# Brickster_8884bt_Receiver.net
KiCad netlist of a schematic drawn in EAGLE
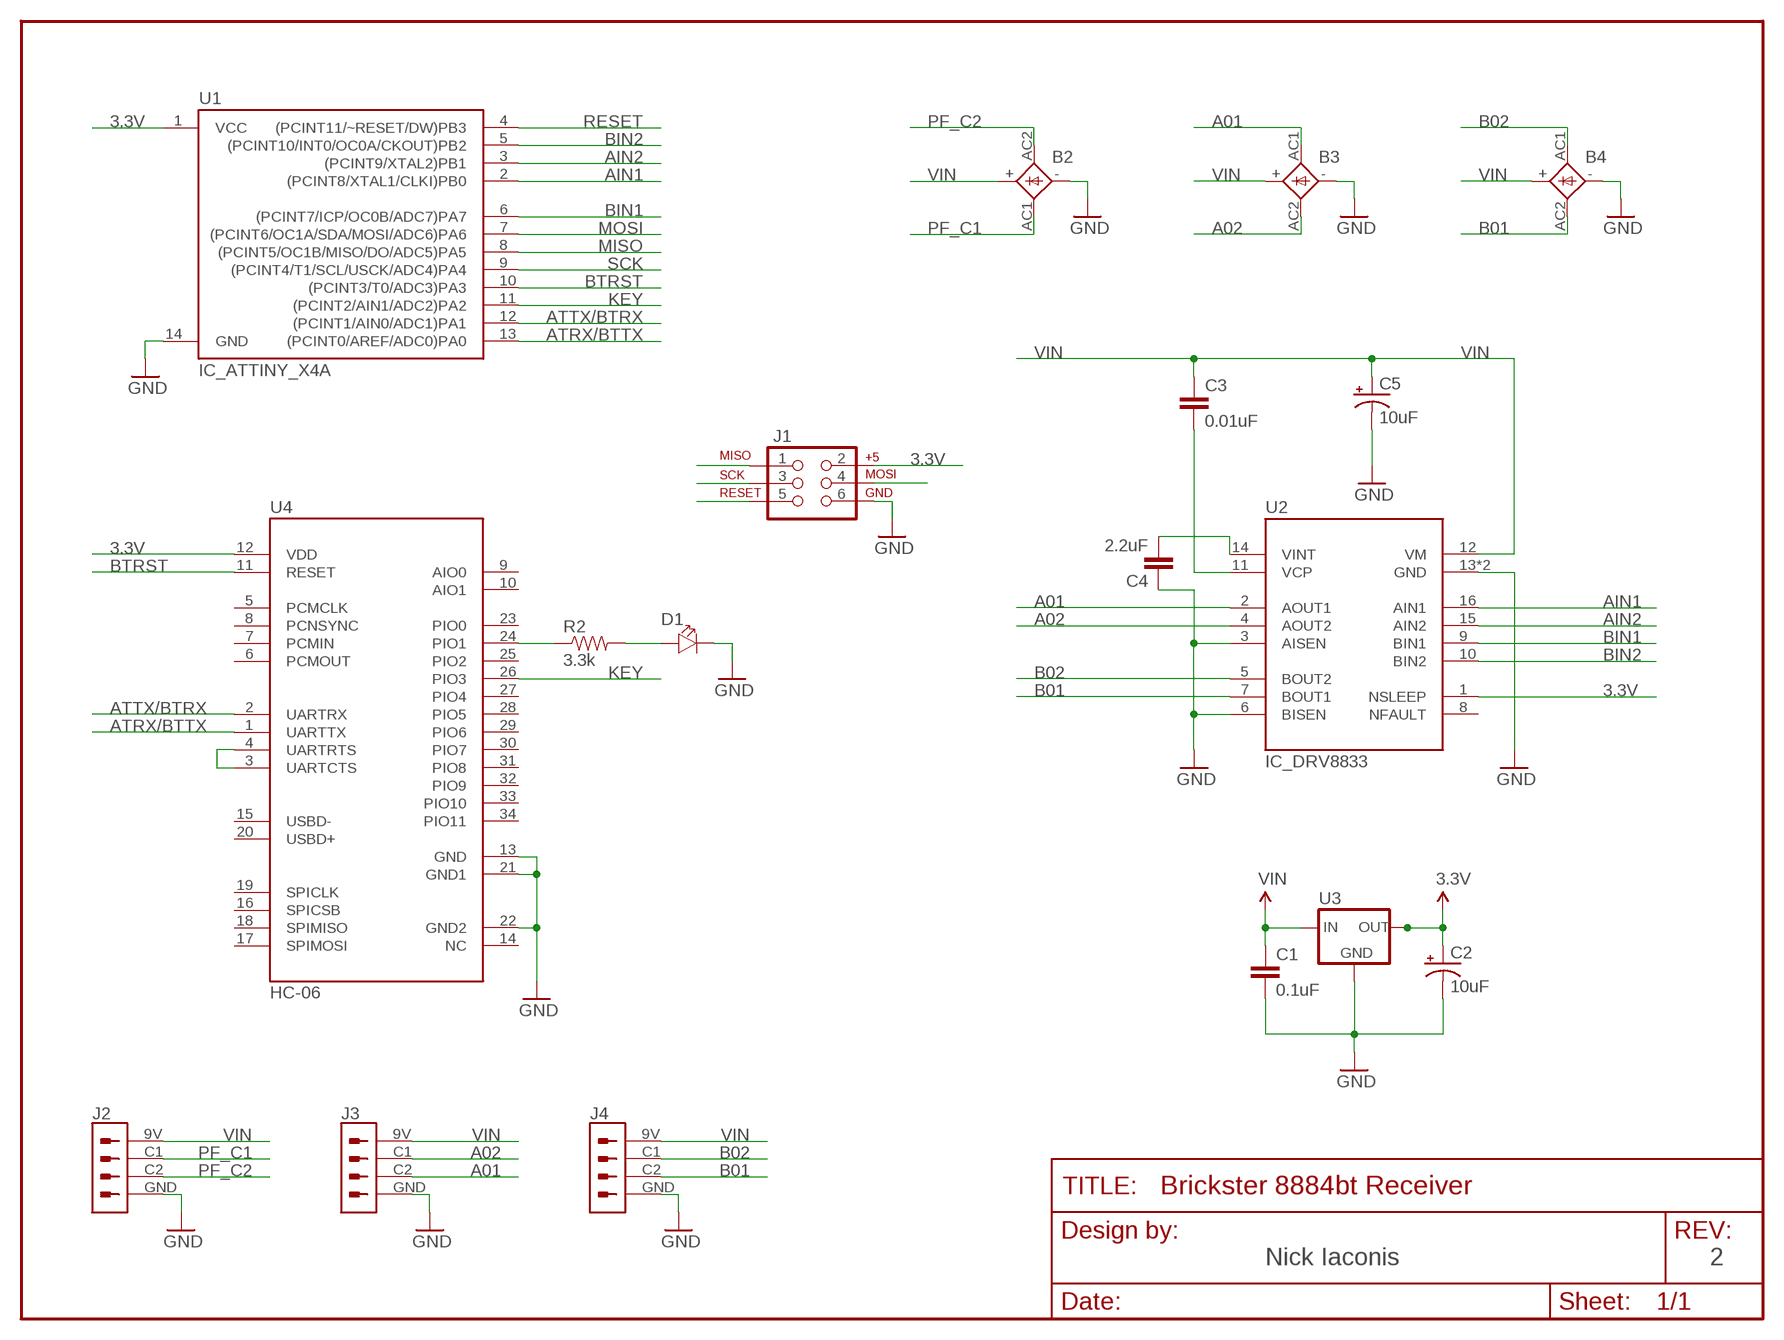
[diagram p0: schematic, sheet 1]

(export (version "E")
  (design (tool "Eeschema 10.0.6"))
  (components
    (comp (ref "B2")
      (value "B_CDBHM240L-HF")
      (footprint "eagle-import:MBS-2")
      (libsource (lib "eagle-import") (part "B_CDBHM240L-HF"))
    )
    (comp (ref "B3")
      (value "B_CDBHM240L-HF")
      (footprint "eagle-import:MBS-2")
      (libsource (lib "eagle-import") (part "B_CDBHM240L-HF"))
    )
    (comp (ref "B4")
      (value "B_CDBHM240L-HF")
      (footprint "eagle-import:MBS-2")
      (libsource (lib "eagle-import") (part "B_CDBHM240L-HF"))
    )
    (comp (ref "C1")
      (value "0.1uF")
      (footprint "eagle-import:0805")
      (libsource (lib "eagle-import") (part "C0805"))
    )
    (comp (ref "C2")
      (value "10uF")
      (footprint "eagle-import:1206")
      (libsource (lib "eagle-import") (part "C_POL"))
    )
    (comp (ref "C3")
      (value "0.01uF")
      (footprint "eagle-import:0805")
      (libsource (lib "eagle-import") (part "C0805"))
    )
    (comp (ref "C4")
      (value "2.2uF")
      (footprint "eagle-import:0805")
      (libsource (lib "eagle-import") (part "C0805"))
    )
    (comp (ref "C5")
      (value "10uF")
      (footprint "eagle-import:1206")
      (libsource (lib "eagle-import") (part "C_POL"))
    )
    (comp (ref "D1")
      (value "LED0805")
      (footprint "eagle-import:0805_POL")
      (libsource (lib "eagle-import") (part "LED0805"))
    )
    (comp (ref "J1")
      (value "AVR_SPI_PRG_6NS")
      (footprint "eagle-import:2X3-NS")
      (libsource (lib "eagle-import") (part "AVR_SPI_PRG_6NS"))
    )
    (comp (ref "J2")
      (value "CON_PF_SMD")
      (footprint "eagle-import:SMD_PF")
      (libsource (lib "eagle-import") (part "CON_PF_SMD"))
    )
    (comp (ref "J3")
      (value "CON_PF_SMD")
      (footprint "eagle-import:SMD_PF")
      (libsource (lib "eagle-import") (part "CON_PF_SMD"))
    )
    (comp (ref "J4")
      (value "CON_PF_SMD")
      (footprint "eagle-import:SMD_PF")
      (libsource (lib "eagle-import") (part "CON_PF_SMD"))
    )
    (comp (ref "R2")
      (value "3.3k")
      (footprint "eagle-import:0805")
      (libsource (lib "eagle-import") (part "R0805"))
    )
    (comp (ref "U1")
      (value "IC_ATTINY_X4A")
      (footprint "eagle-import:14S1")
      (libsource (lib "eagle-import") (part "IC_ATTINY_X4A"))
    )
    (comp (ref "U2")
      (value "IC_DRV8833")
      (footprint "eagle-import:PWP_R-PDSO-G16")
      (libsource (lib "eagle-import") (part "IC_DRV8833"))
    )
    (comp (ref "U3")
      (value "IC_RT9164A")
      (footprint "eagle-import:SOT223")
      (libsource (lib "eagle-import") (part "IC_RT9164A"))
    )
    (comp (ref "U4")
      (value "HC-06")
      (footprint "eagle-import:BLUETOOTH_SMD")
      (libsource (lib "eagle-import") (part "HC-06"))
    )
  )
  (nets
    (net (code "1") (name "/A01") (class "Default")
      (node (ref "B3") (pin "AC1") (pinfunction "AC1_AC1") (pintype "passive"))
      (node (ref "J3") (pin "C2") (pinfunction "P$3_C2") (pintype "bidirectional"))
      (node (ref "U2") (pin "2") (pinfunction "AOUT1_2") (pintype "bidirectional"))
    )
    (net (code "2") (name "/A02") (class "Default")
      (node (ref "B3") (pin "AC2") (pinfunction "AC2_AC2") (pintype "passive"))
      (node (ref "J3") (pin "C1") (pinfunction "P$2_C1") (pintype "bidirectional"))
      (node (ref "U2") (pin "4") (pinfunction "AOUT2_4") (pintype "bidirectional"))
    )
    (net (code "3") (name "/AIN1") (class "Default")
      (node (ref "U1") (pin "2") (pinfunction "(PCINT8/XTAL1/CLKI)PB0_2") (pintype "bidirectional"))
      (node (ref "U2") (pin "16") (pinfunction "AIN1_16") (pintype "bidirectional"))
    )
    (net (code "4") (name "/AIN2") (class "Default")
      (node (ref "U1") (pin "3") (pinfunction "(PCINT9/XTAL2)PB1_3") (pintype "bidirectional"))
      (node (ref "U2") (pin "15") (pinfunction "AIN2_15") (pintype "bidirectional"))
    )
    (net (code "5") (name "/ATRX{slash}BTTX") (class "Default")
      (node (ref "U1") (pin "13") (pinfunction "(PCINT0/AREF/ADC0)PA0_13") (pintype "bidirectional"))
      (node (ref "U4") (pin "1") (pinfunction "UARTTX_1") (pintype "bidirectional"))
    )
    (net (code "6") (name "/ATTX{slash}BTRX") (class "Default")
      (node (ref "U1") (pin "12") (pinfunction "(PCINT1/AIN0/ADC1)PA1_12") (pintype "bidirectional"))
      (node (ref "U4") (pin "2") (pinfunction "UARTRX_2") (pintype "bidirectional"))
    )
    (net (code "7") (name "/B01") (class "Default")
      (node (ref "B4") (pin "AC2") (pinfunction "AC2_AC2") (pintype "passive"))
      (node (ref "J4") (pin "C2") (pinfunction "P$3_C2") (pintype "bidirectional"))
      (node (ref "U2") (pin "7") (pinfunction "BOUT1_7") (pintype "bidirectional"))
    )
    (net (code "8") (name "/B02") (class "Default")
      (node (ref "B4") (pin "AC1") (pinfunction "AC1_AC1") (pintype "passive"))
      (node (ref "J4") (pin "C1") (pinfunction "P$2_C1") (pintype "bidirectional"))
      (node (ref "U2") (pin "5") (pinfunction "BOUT2_5") (pintype "bidirectional"))
    )
    (net (code "9") (name "/BIN1") (class "Default")
      (node (ref "U1") (pin "6") (pinfunction "(PCINT7/ICP/OC0B/ADC7)PA7_6") (pintype "bidirectional"))
      (node (ref "U2") (pin "9") (pinfunction "BIN1_9") (pintype "bidirectional"))
    )
    (net (code "10") (name "/BIN2") (class "Default")
      (node (ref "U1") (pin "5") (pinfunction "(PCINT10/INT0/OC0A/CKOUT)PB2_5") (pintype "bidirectional"))
      (node (ref "U2") (pin "10") (pinfunction "BIN2_10") (pintype "bidirectional"))
    )
    (net (code "11") (name "/BTRST") (class "Default")
      (node (ref "U1") (pin "10") (pinfunction "(PCINT3/T0/ADC3)PA3_10") (pintype "bidirectional"))
      (node (ref "U4") (pin "11") (pinfunction "RESET_11") (pintype "bidirectional"))
    )
    (net (code "12") (name "/KEY") (class "Default")
      (node (ref "U1") (pin "11") (pinfunction "(PCINT2/AIN1/ADC2)PA2_11") (pintype "bidirectional"))
      (node (ref "U4") (pin "26") (pinfunction "PIO3_26") (pintype "bidirectional"))
    )
    (net (code "13") (name "/MISO") (class "Default")
      (node (ref "J1") (pin "1") (pinfunction "1_1") (pintype "passive"))
      (node (ref "U1") (pin "8") (pinfunction "(PCINT5/OC1B/MISO/DO/ADC5)PA5_8") (pintype "bidirectional"))
    )
    (net (code "14") (name "/MOSI") (class "Default")
      (node (ref "J1") (pin "4") (pinfunction "4_4") (pintype "passive"))
      (node (ref "U1") (pin "7") (pinfunction "(PCINT6/OC1A/SDA/MOSI/ADC6)PA6_7") (pintype "bidirectional"))
    )
    (net (code "15") (name "/PF_C1") (class "Default")
      (node (ref "B2") (pin "AC1") (pinfunction "AC1_AC1") (pintype "passive"))
      (node (ref "J2") (pin "C1") (pinfunction "P$2_C1") (pintype "bidirectional"))
    )
    (net (code "16") (name "/PF_C2") (class "Default")
      (node (ref "B2") (pin "AC2") (pinfunction "AC2_AC2") (pintype "passive"))
      (node (ref "J2") (pin "C2") (pinfunction "P$3_C2") (pintype "bidirectional"))
    )
    (net (code "17") (name "/RESET") (class "Default")
      (node (ref "J1") (pin "5") (pinfunction "5_5") (pintype "passive"))
      (node (ref "U1") (pin "4") (pinfunction "(PCINT11/~{RESET/DW})PB3_4") (pintype "bidirectional"))
    )
    (net (code "18") (name "/SCK") (class "Default")
      (node (ref "J1") (pin "3") (pinfunction "3_3") (pintype "passive"))
      (node (ref "U1") (pin "9") (pinfunction "(PCINT4/T1/SCL/USCK/ADC4)PA4_9") (pintype "bidirectional"))
    )
    (net (code "19") (name "3.3V") (class "Default")
      (node (ref "C2") (pin "1") (pinfunction "+_1") (pintype "passive"))
      (node (ref "J1") (pin "2") (pinfunction "2_2") (pintype "passive"))
      (node (ref "U1") (pin "1") (pinfunction "VCC_1") (pintype "bidirectional"))
      (node (ref "U2") (pin "1") (pinfunction "NSLEEP_1") (pintype "bidirectional"))
      (node (ref "U3") (pin "2") (pinfunction "OUT_2") (pintype "output"))
      (node (ref "U3") (pin "4") (pinfunction "P$1_4") (pintype "output"))
      (node (ref "U4") (pin "12") (pinfunction "VDD_12") (pintype "bidirectional"))
    )
    (net (code "20") (name "GND") (class "Default")
      (node (ref "B2") (pin "-") (pinfunction "-_-") (pintype "passive"))
      (node (ref "B3") (pin "-") (pinfunction "-_-") (pintype "passive"))
      (node (ref "B4") (pin "-") (pinfunction "-_-") (pintype "passive"))
      (node (ref "C1") (pin "P$2") (pinfunction "2_P$2") (pintype "passive"))
      (node (ref "C2") (pin "2") (pinfunction "-_2") (pintype "passive"))
      (node (ref "C4") (pin "P$1") (pinfunction "1_P$1") (pintype "passive"))
      (node (ref "C5") (pin "2") (pinfunction "-_2") (pintype "passive"))
      (node (ref "D1") (pin "P$1") (pinfunction "P$2_P$1") (pintype "output"))
      (node (ref "J1") (pin "6") (pinfunction "6_6") (pintype "passive"))
      (node (ref "J2") (pin "GND") (pinfunction "P$4_GND") (pintype "bidirectional"))
      (node (ref "J3") (pin "GND") (pinfunction "P$4_GND") (pintype "bidirectional"))
      (node (ref "J4") (pin "GND") (pinfunction "P$4_GND") (pintype "bidirectional"))
      (node (ref "U1") (pin "14") (pinfunction "GND_14") (pintype "bidirectional"))
      (node (ref "U2") (pin "13") (pinfunction "GND_13") (pintype "bidirectional"))
      (node (ref "U2") (pin "17") (pinfunction "GND_17") (pintype "bidirectional"))
      (node (ref "U2") (pin "3") (pinfunction "AISEN_3") (pintype "bidirectional"))
      (node (ref "U2") (pin "6") (pinfunction "BISEN_6") (pintype "bidirectional"))
      (node (ref "U3") (pin "1") (pinfunction "GND_1") (pintype "input"))
      (node (ref "U4") (pin "13") (pinfunction "GND_13") (pintype "bidirectional"))
      (node (ref "U4") (pin "21") (pinfunction "GND1_21") (pintype "bidirectional"))
      (node (ref "U4") (pin "22") (pinfunction "GND2_22") (pintype "bidirectional"))
    )
    (net (code "21") (name "Net-(C3-2)") (class "Default")
      (node (ref "C3") (pin "P$2") (pinfunction "2_P$2") (pintype "passive"))
      (node (ref "U2") (pin "11") (pinfunction "VCP_11") (pintype "bidirectional"))
    )
    (net (code "22") (name "Net-(C4-2)") (class "Default")
      (node (ref "C4") (pin "P$2") (pinfunction "2_P$2") (pintype "passive"))
      (node (ref "U2") (pin "14") (pinfunction "VINT_14") (pintype "bidirectional"))
    )
    (net (code "23") (name "Net-(D1-P$1)") (class "Default")
      (node (ref "D1") (pin "P$2") (pinfunction "P$1_P$2") (pintype "input"))
      (node (ref "R2") (pin "P$2") (pinfunction "2_P$2") (pintype "passive"))
    )
    (net (code "24") (name "Net-(R2-1)") (class "Default")
      (node (ref "R2") (pin "P$1") (pinfunction "1_P$1") (pintype "passive"))
      (node (ref "U4") (pin "24") (pinfunction "PIO1_24") (pintype "bidirectional"))
    )
    (net (code "25") (name "Net-(U4-UARTCTS)") (class "Default")
      (node (ref "U4") (pin "3") (pinfunction "UARTCTS_3") (pintype "bidirectional"))
      (node (ref "U4") (pin "4") (pinfunction "UARTRTS_4") (pintype "bidirectional"))
    )
    (net (code "26") (name "VIN") (class "Default")
      (node (ref "B2") (pin "+") (pinfunction "+_+") (pintype "passive"))
      (node (ref "B3") (pin "+") (pinfunction "+_+") (pintype "passive"))
      (node (ref "B4") (pin "+") (pinfunction "+_+") (pintype "passive"))
      (node (ref "C1") (pin "P$1") (pinfunction "1_P$1") (pintype "passive"))
      (node (ref "C3") (pin "P$1") (pinfunction "1_P$1") (pintype "passive"))
      (node (ref "C5") (pin "1") (pinfunction "+_1") (pintype "passive"))
      (node (ref "J2") (pin "9V") (pinfunction "P$1_9V") (pintype "bidirectional"))
      (node (ref "J3") (pin "9V") (pinfunction "P$1_9V") (pintype "bidirectional"))
      (node (ref "J4") (pin "9V") (pinfunction "P$1_9V") (pintype "bidirectional"))
      (node (ref "U2") (pin "12") (pinfunction "VM_12") (pintype "bidirectional"))
      (node (ref "U3") (pin "3") (pinfunction "IN_3") (pintype "input"))
    )
    (net (code "27") (name "unconnected-(U2-NFAULT-Pad8)") (class "Default")
      (node (ref "U2") (pin "8") (pinfunction "NFAULT_8") (pintype "bidirectional"))
    )
    (net (code "28") (name "unconnected-(U4-AIO0-Pad9)") (class "Default")
      (node (ref "U4") (pin "9") (pinfunction "AIO0_9") (pintype "bidirectional"))
    )
    (net (code "29") (name "unconnected-(U4-AIO1-Pad10)") (class "Default")
      (node (ref "U4") (pin "10") (pinfunction "AIO1_10") (pintype "bidirectional"))
    )
    (net (code "30") (name "unconnected-(U4-NC-Pad14)") (class "Default")
      (node (ref "U4") (pin "14") (pinfunction "NC_14") (pintype "bidirectional"))
    )
    (net (code "31") (name "unconnected-(U4-PCMCLK-Pad5)") (class "Default")
      (node (ref "U4") (pin "5") (pinfunction "PCMCLK_5") (pintype "bidirectional"))
    )
    (net (code "32") (name "unconnected-(U4-PCMIN-Pad7)") (class "Default")
      (node (ref "U4") (pin "7") (pinfunction "PCMIN_7") (pintype "bidirectional"))
    )
    (net (code "33") (name "unconnected-(U4-PCMOUT-Pad6)") (class "Default")
      (node (ref "U4") (pin "6") (pinfunction "PCMOUT_6") (pintype "bidirectional"))
    )
    (net (code "34") (name "unconnected-(U4-PCNSYNC-Pad8)") (class "Default")
      (node (ref "U4") (pin "8") (pinfunction "PCNSYNC_8") (pintype "bidirectional"))
    )
    (net (code "35") (name "unconnected-(U4-PIO0-Pad23)") (class "Default")
      (node (ref "U4") (pin "23") (pinfunction "PIO0_23") (pintype "bidirectional"))
    )
    (net (code "36") (name "unconnected-(U4-PIO2-Pad25)") (class "Default")
      (node (ref "U4") (pin "25") (pinfunction "PIO2_25") (pintype "bidirectional"))
    )
    (net (code "37") (name "unconnected-(U4-PIO4-Pad27)") (class "Default")
      (node (ref "U4") (pin "27") (pinfunction "PIO4_27") (pintype "bidirectional"))
    )
    (net (code "38") (name "unconnected-(U4-PIO5-Pad28)") (class "Default")
      (node (ref "U4") (pin "28") (pinfunction "PIO5_28") (pintype "bidirectional"))
    )
    (net (code "39") (name "unconnected-(U4-PIO6-Pad29)") (class "Default")
      (node (ref "U4") (pin "29") (pinfunction "PIO6_29") (pintype "bidirectional"))
    )
    (net (code "40") (name "unconnected-(U4-PIO7-Pad30)") (class "Default")
      (node (ref "U4") (pin "30") (pinfunction "PIO7_30") (pintype "bidirectional"))
    )
    (net (code "41") (name "unconnected-(U4-PIO8-Pad31)") (class "Default")
      (node (ref "U4") (pin "31") (pinfunction "PIO8_31") (pintype "bidirectional"))
    )
    (net (code "42") (name "unconnected-(U4-PIO9-Pad32)") (class "Default")
      (node (ref "U4") (pin "32") (pinfunction "PIO9_32") (pintype "bidirectional"))
    )
    (net (code "43") (name "unconnected-(U4-PIO10-Pad33)") (class "Default")
      (node (ref "U4") (pin "33") (pinfunction "PIO10_33") (pintype "bidirectional"))
    )
    (net (code "44") (name "unconnected-(U4-PIO11-Pad34)") (class "Default")
      (node (ref "U4") (pin "34") (pinfunction "PIO11_34") (pintype "bidirectional"))
    )
    (net (code "45") (name "unconnected-(U4-SPICLK-Pad19)") (class "Default")
      (node (ref "U4") (pin "19") (pinfunction "SPICLK_19") (pintype "bidirectional"))
    )
    (net (code "46") (name "unconnected-(U4-SPICSB-Pad16)") (class "Default")
      (node (ref "U4") (pin "16") (pinfunction "SPICSB_16") (pintype "bidirectional"))
    )
    (net (code "47") (name "unconnected-(U4-SPIMISO-Pad18)") (class "Default")
      (node (ref "U4") (pin "18") (pinfunction "SPIMISO_18") (pintype "bidirectional"))
    )
    (net (code "48") (name "unconnected-(U4-SPIMOSI-Pad17)") (class "Default")
      (node (ref "U4") (pin "17") (pinfunction "SPIMOSI_17") (pintype "bidirectional"))
    )
    (net (code "49") (name "unconnected-(U4-USBD+-Pad20)") (class "Default")
      (node (ref "U4") (pin "20") (pinfunction "USBD+_20") (pintype "bidirectional"))
    )
    (net (code "50") (name "unconnected-(U4-USBD--Pad15)") (class "Default")
      (node (ref "U4") (pin "15") (pinfunction "USBD-_15") (pintype "bidirectional"))
    )
  )
)
